# GripperBoard.net
KiCad netlist of a schematic drawn in EAGLE
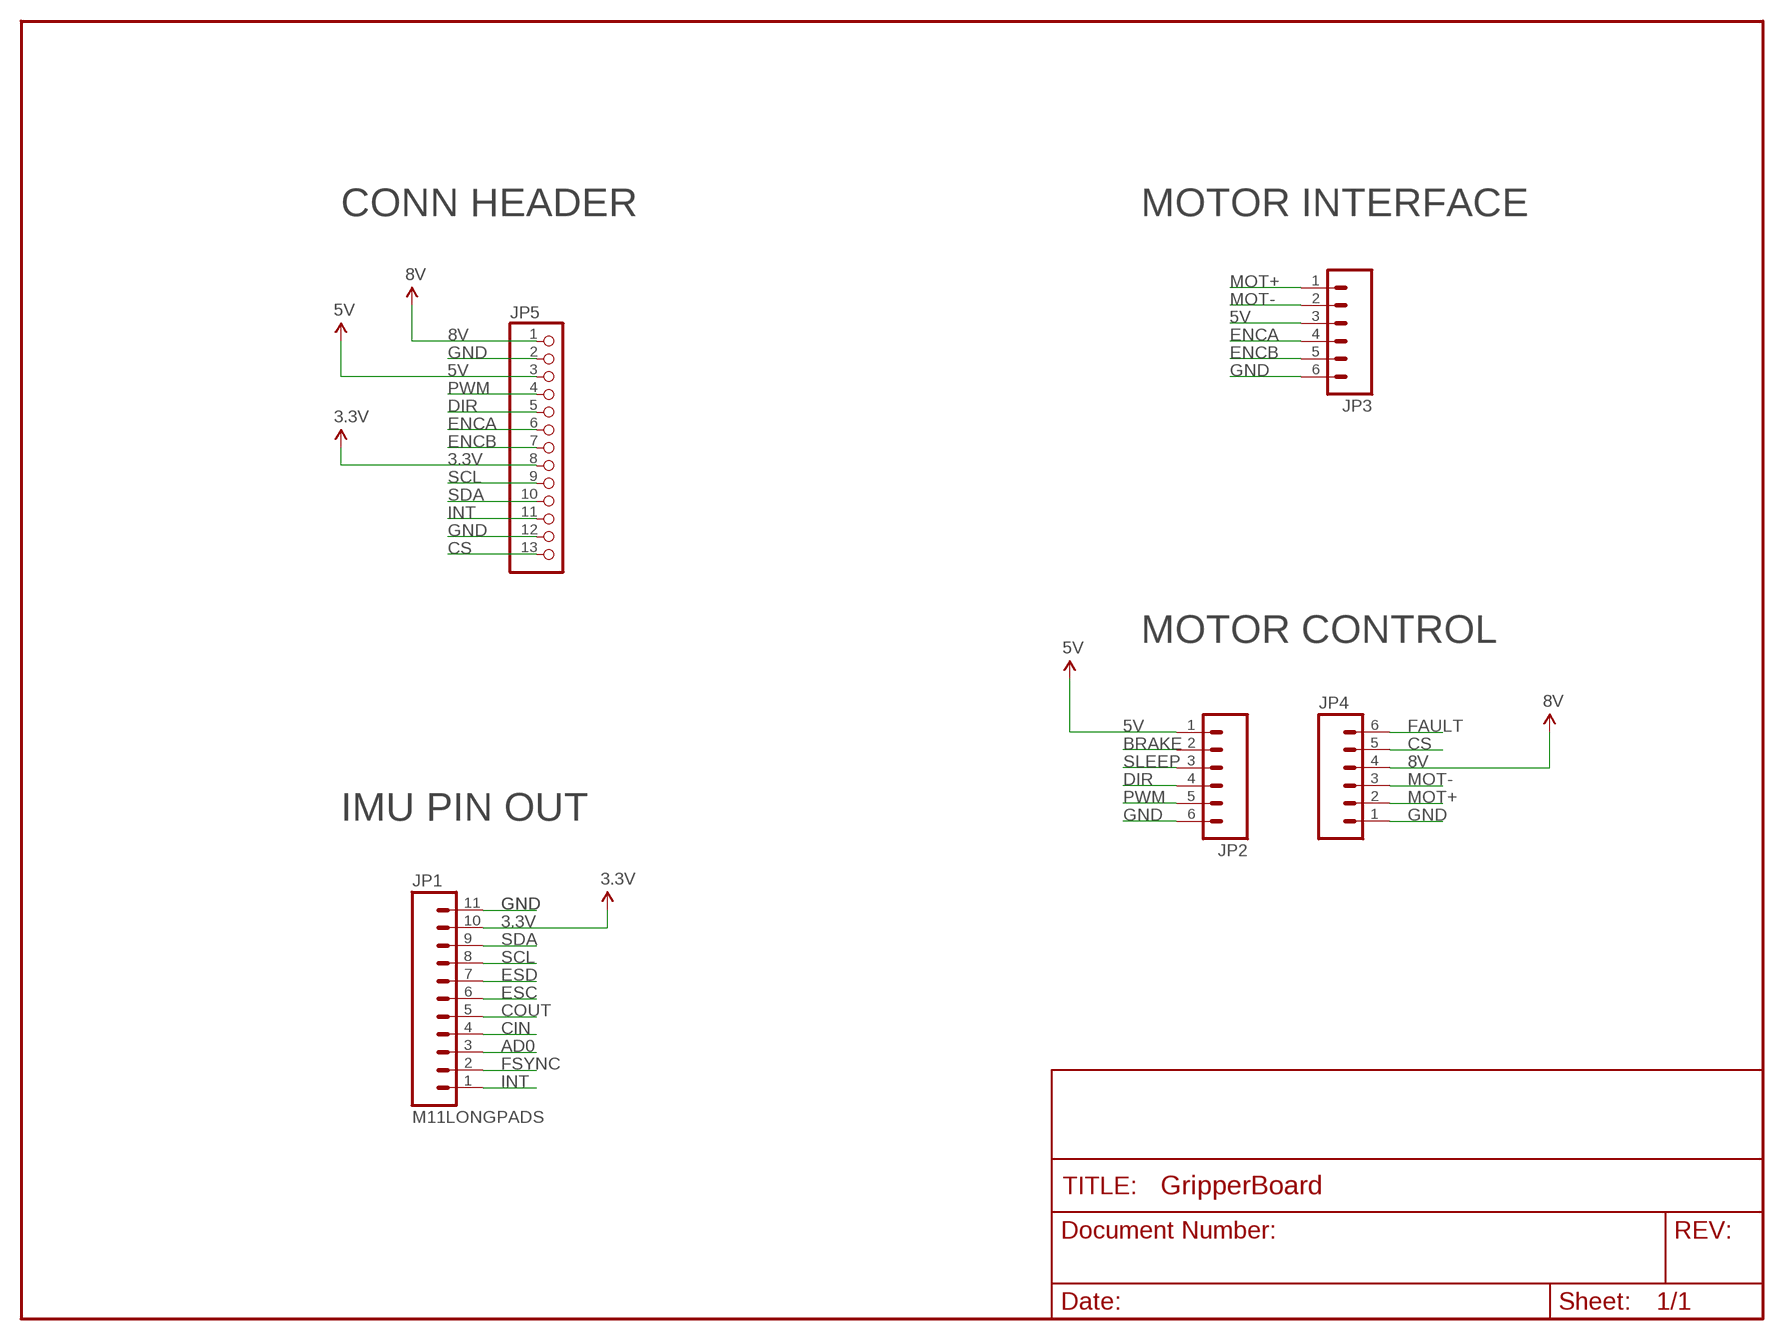
[diagram p0: schematic, sheet 1]

(export (version "E")
  (design (tool "Eeschema 10.0.6"))
  (components
    (comp (ref "JP1")
      (value "M11LONGPADS")
      (footprint "eagle-import:1X11_LONGPADS")
      (libsource (lib "eagle-import") (part "M11LONGPADS"))
    )
    (comp (ref "JP2")
      (value "M06LONGPADS")
      (footprint "eagle-import:1X06_LONGPADS")
      (libsource (lib "eagle-import") (part "M06LONGPADS"))
    )
    (comp (ref "JP3")
      (value "M06LONGPADS")
      (footprint "eagle-import:1X06_LONGPADS")
      (libsource (lib "eagle-import") (part "M06LONGPADS"))
    )
    (comp (ref "JP4")
      (value "M06LONGPADS")
      (footprint "eagle-import:1X06_LONGPADS")
      (libsource (lib "eagle-import") (part "M06LONGPADS"))
    )
    (comp (ref "JP5")
      (value "PINHD-1X13")
      (footprint "eagle-import:1X13")
      (libsource (lib "eagle-import") (part "PINHD-1X13"))
    )
  )
  (nets
    (net (code "1") (name "/AD0") (class "Default")
      (node (ref "JP1") (pin "3") (pinfunction "3_3") (pintype "passive"))
    )
    (net (code "2") (name "/BRAKE") (class "Default")
      (node (ref "JP2") (pin "2") (pinfunction "2_2") (pintype "passive"))
    )
    (net (code "3") (name "/CIN") (class "Default")
      (node (ref "JP1") (pin "4") (pinfunction "4_4") (pintype "passive"))
    )
    (net (code "4") (name "/COUT") (class "Default")
      (node (ref "JP1") (pin "5") (pinfunction "5_5") (pintype "passive"))
    )
    (net (code "5") (name "/CS") (class "Default")
      (node (ref "JP4") (pin "5") (pinfunction "5_5") (pintype "passive"))
      (node (ref "JP5") (pin "13") (pinfunction "13_13") (pintype "passive"))
    )
    (net (code "6") (name "/DIR") (class "Default")
      (node (ref "JP2") (pin "4") (pinfunction "4_4") (pintype "passive"))
      (node (ref "JP5") (pin "5") (pinfunction "5_5") (pintype "passive"))
    )
    (net (code "7") (name "/ENCA") (class "Default")
      (node (ref "JP3") (pin "4") (pinfunction "4_4") (pintype "passive"))
      (node (ref "JP5") (pin "6") (pinfunction "6_6") (pintype "passive"))
    )
    (net (code "8") (name "/ENCB") (class "Default")
      (node (ref "JP3") (pin "5") (pinfunction "5_5") (pintype "passive"))
      (node (ref "JP5") (pin "7") (pinfunction "7_7") (pintype "passive"))
    )
    (net (code "9") (name "/ESC") (class "Default")
      (node (ref "JP1") (pin "6") (pinfunction "6_6") (pintype "passive"))
    )
    (net (code "10") (name "/ESD") (class "Default")
      (node (ref "JP1") (pin "7") (pinfunction "7_7") (pintype "passive"))
    )
    (net (code "11") (name "/FAULT") (class "Default")
      (node (ref "JP4") (pin "6") (pinfunction "6_6") (pintype "passive"))
    )
    (net (code "12") (name "/FSYNC") (class "Default")
      (node (ref "JP1") (pin "2") (pinfunction "2_2") (pintype "passive"))
    )
    (net (code "13") (name "/GND") (class "Default")
      (node (ref "JP1") (pin "11") (pinfunction "11_11") (pintype "passive"))
      (node (ref "JP2") (pin "6") (pinfunction "6_6") (pintype "passive"))
      (node (ref "JP3") (pin "6") (pinfunction "6_6") (pintype "passive"))
      (node (ref "JP4") (pin "1") (pinfunction "1_1") (pintype "passive"))
      (node (ref "JP5") (pin "12") (pinfunction "12_12") (pintype "passive"))
      (node (ref "JP5") (pin "2") (pinfunction "2_2") (pintype "passive"))
    )
    (net (code "14") (name "/INT") (class "Default")
      (node (ref "JP1") (pin "1") (pinfunction "1_1") (pintype "passive"))
      (node (ref "JP5") (pin "11") (pinfunction "11_11") (pintype "passive"))
    )
    (net (code "15") (name "/MOT+") (class "Default")
      (node (ref "JP3") (pin "1") (pinfunction "1_1") (pintype "passive"))
      (node (ref "JP4") (pin "2") (pinfunction "2_2") (pintype "passive"))
    )
    (net (code "16") (name "/MOT-") (class "Default")
      (node (ref "JP3") (pin "2") (pinfunction "2_2") (pintype "passive"))
      (node (ref "JP4") (pin "3") (pinfunction "3_3") (pintype "passive"))
    )
    (net (code "17") (name "/PWM") (class "Default")
      (node (ref "JP2") (pin "5") (pinfunction "5_5") (pintype "passive"))
      (node (ref "JP5") (pin "4") (pinfunction "4_4") (pintype "passive"))
    )
    (net (code "18") (name "/SCL") (class "Default")
      (node (ref "JP1") (pin "8") (pinfunction "8_8") (pintype "passive"))
      (node (ref "JP5") (pin "9") (pinfunction "9_9") (pintype "passive"))
    )
    (net (code "19") (name "/SDA") (class "Default")
      (node (ref "JP1") (pin "9") (pinfunction "9_9") (pintype "passive"))
      (node (ref "JP5") (pin "10") (pinfunction "10_10") (pintype "passive"))
    )
    (net (code "20") (name "/SLEEP") (class "Default")
      (node (ref "JP2") (pin "3") (pinfunction "3_3") (pintype "passive"))
    )
    (net (code "21") (name "3.3V") (class "Default")
      (node (ref "JP1") (pin "10") (pinfunction "10_10") (pintype "passive"))
      (node (ref "JP5") (pin "8") (pinfunction "8_8") (pintype "passive"))
    )
    (net (code "22") (name "5V") (class "Default")
      (node (ref "JP2") (pin "1") (pinfunction "1_1") (pintype "passive"))
      (node (ref "JP3") (pin "3") (pinfunction "3_3") (pintype "passive"))
      (node (ref "JP5") (pin "3") (pinfunction "3_3") (pintype "passive"))
    )
    (net (code "23") (name "8V") (class "Default")
      (node (ref "JP4") (pin "4") (pinfunction "4_4") (pintype "passive"))
      (node (ref "JP5") (pin "1") (pinfunction "1_1") (pintype "passive"))
    )
  )
)
